# DMXController.net
KiCad netlist of a schematic drawn in Altium Designer
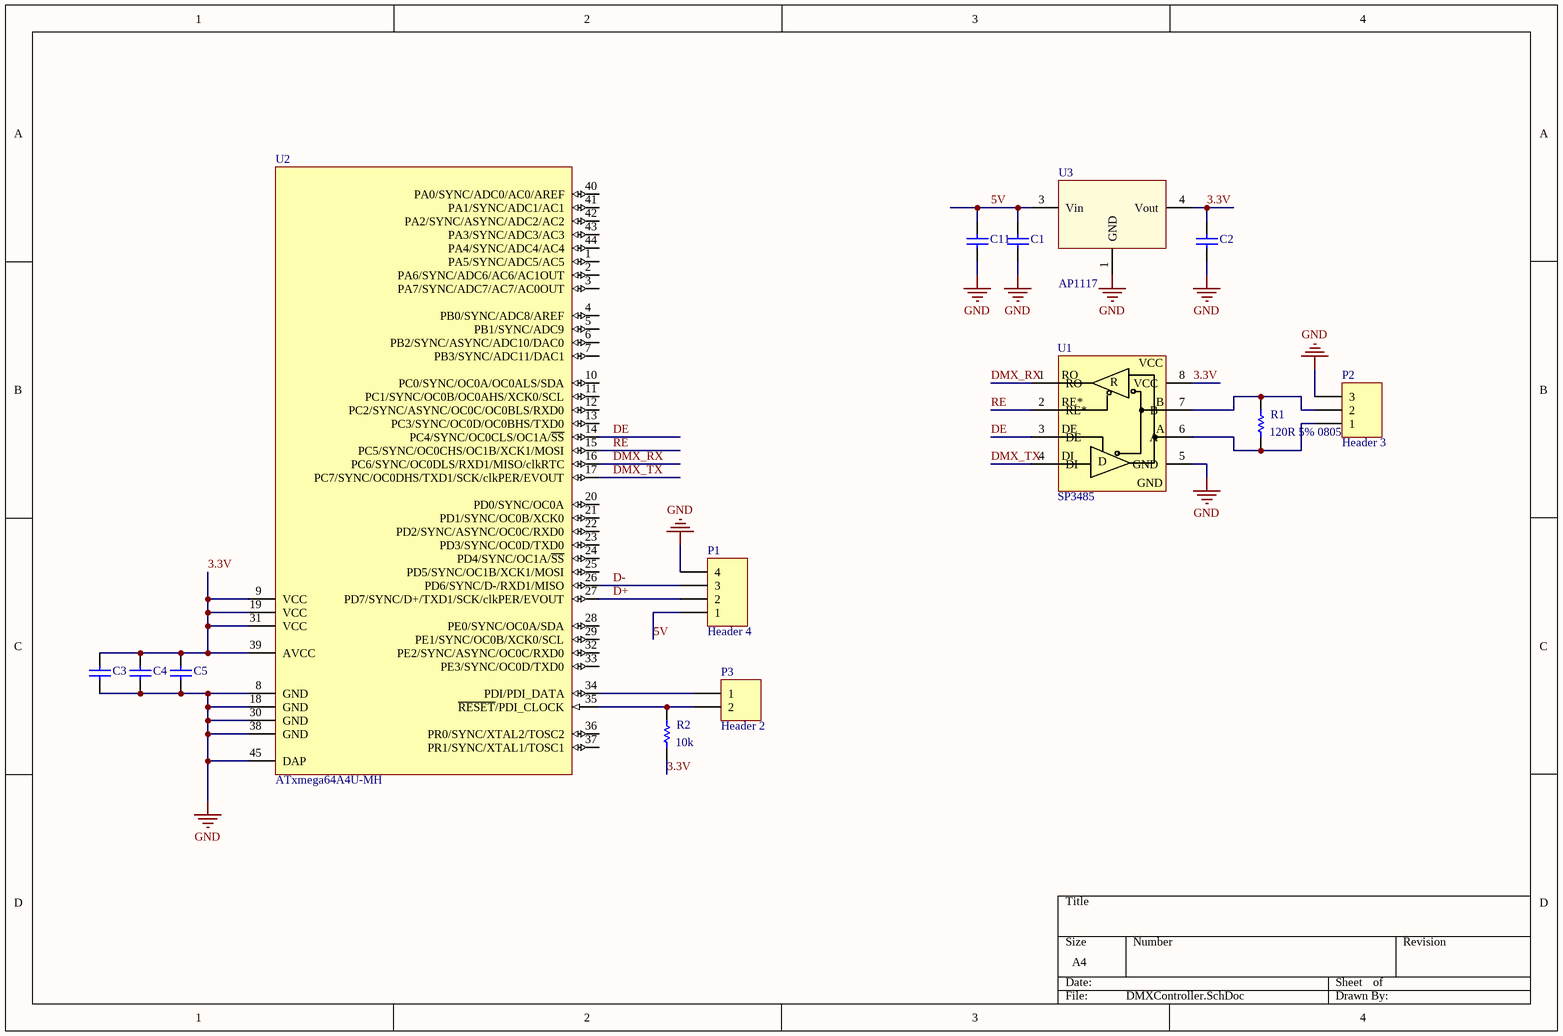
[diagram p0: DMXController.SchDoc]

(export (version "E")
  (design (tool "Eeschema 10.0.6"))
  (components
    (comp (ref "C1")
      (value "10u")
      (footprint "CAPC0805(2012)100_M")
      (description "CAP 1uF 10V ±10% 0805 (2012 Metric) Thickness 1mm SMD")
      (fields (field (name "TOLERANCE") "±10%"))
      (libsource (lib "Altium Content Vault") (part "CMP-1036-04739-1"))
    )
    (comp (ref "C2")
      (value "22u")
      (footprint "CAPC0805(2012)100_M")
      (description "CAP 1uF 10V ±10% 0805 (2012 Metric) Thickness 1mm SMD")
      (fields (field (name "TOLERANCE") "±10%"))
      (libsource (lib "Altium Content Vault") (part "CMP-1036-04739-1"))
    )
    (comp (ref "C3")
      (value "100n")
      (footprint "CAPC0805(2012)100_M")
      (description "CAP 1uF 10V ±10% 0805 (2012 Metric) Thickness 1mm SMD")
      (fields (field (name "TOLERANCE") "±10%"))
      (libsource (lib "Altium Content Vault") (part "CMP-1036-04739-1"))
    )
    (comp (ref "C4")
      (value "100n")
      (footprint "CAPC0805(2012)100_M")
      (description "CAP 1uF 10V ±10% 0805 (2012 Metric) Thickness 1mm SMD")
      (fields (field (name "TOLERANCE") "±10%"))
      (libsource (lib "Altium Content Vault") (part "CMP-1036-04739-1"))
    )
    (comp (ref "C5")
      (value "100n")
      (footprint "CAPC0805(2012)100_M")
      (description "CAP 1uF 10V ±10% 0805 (2012 Metric) Thickness 1mm SMD")
      (fields (field (name "TOLERANCE") "±10%"))
      (libsource (lib "Altium Content Vault") (part "CMP-1036-04739-1"))
    )
    (comp (ref "C11")
      (value "10u")
      (footprint "CAPC0805(2012)100_M")
      (description "CAP 1uF 10V ±10% 0805 (2012 Metric) Thickness 1mm SMD")
      (fields (field (name "TOLERANCE") "±10%"))
      (libsource (lib "Altium Content Vault") (part "CMP-1036-04739-1"))
    )
    (comp (ref "P1")
      (value "Header 4")
      (footprint "HDR1X4")
      (description "Header, 4-Pin")
      (fields (field (name "PUBLISHER") "Altium Limited"))
      (libsource (lib "Miscellaneous Connectors") (part "Header 4"))
    )
    (comp (ref "P2")
      (value "Header 3")
      (footprint "HDR1X3")
      (description "Header, 3-Pin")
      (fields (field (name "PUBLISHER") "Altium Limited"))
      (libsource (lib "Miscellaneous Connectors") (part "Header 3"))
    )
    (comp (ref "P3")
      (value "Header 2")
      (footprint "HDR1X2")
      (description "Header, 2-Pin")
      (fields (field (name "PUBLISHER") "Altium Limited"))
      (libsource (lib "Miscellaneous Connectors") (part "Header 2"))
    )
    (comp (ref "R1")
      (value "120R 5% 0805(2012)")
      (footprint "RESC0805(2012)_N")
      (description "120R 0.125W 5% 0805 (2012 Metric)  SMD")
      (fields (field (name "TOLERANCE") "5 %") (field (name "POWER") "0.125 W"))
      (libsource (lib "Altium Content Vault") (part "RES"))
    )
    (comp (ref "R2")
      (value "10k")
      (footprint "RESC0805(2012)_N")
      (description "120R 0.125W 5% 0805 (2012 Metric)  SMD")
      (fields (field (name "TOLERANCE") "5 %") (field (name "POWER") "0.125 W"))
      (libsource (lib "Altium Content Vault") (part "CMP-1013-00052-1"))
    )
    (comp (ref "U1") (value "SP3485") (footprint "SOIC8") (libsource (lib "Schlib1") (part "SP3485")))
    (comp (ref "U2")
      (value "ATxmega64A4U-MH")
      (footprint "44M1_L")
      (libsource (lib "Altium Content Vault") (part "MC-8B-ATXM16A4U-SQ45"))
    )
    (comp (ref "U3") (value "AP1117") (footprint "SOT-223") (libsource (lib "Schlib1") (part "AP1117")))
  )
  (nets
    (net (code "1") (name "/3.3V") (class "Default")
      (node (ref "C2") (pin "2") (pinfunction "2_2") (pintype "passive"))
      (node (ref "C3") (pin "2") (pinfunction "2_2") (pintype "passive"))
      (node (ref "C4") (pin "2") (pinfunction "2_2") (pintype "passive"))
      (node (ref "C5") (pin "2") (pinfunction "2_2") (pintype "passive"))
      (node (ref "R2") (pin "1") (pinfunction "1_1") (pintype "passive"))
      (node (ref "U1") (pin "8") (pinfunction "VCC_8") (pintype "passive"))
      (node (ref "U2") (pin "19") (pinfunction "VCC_19") (pintype "power_in"))
      (node (ref "U2") (pin "31") (pinfunction "VCC_31") (pintype "power_in"))
      (node (ref "U2") (pin "39") (pinfunction "AVCC_39") (pintype "power_in"))
      (node (ref "U2") (pin "9") (pinfunction "VCC_9") (pintype "power_in"))
      (node (ref "U3") (pin "4") (pinfunction "Vout_4") (pintype "passive"))
    )
    (net (code "2") (name "/5V") (class "Default")
      (node (ref "C1") (pin "2") (pinfunction "2_2") (pintype "passive"))
      (node (ref "C11") (pin "2") (pinfunction "2_2") (pintype "passive"))
      (node (ref "P1") (pin "1") (pinfunction "1_1") (pintype "passive"))
      (node (ref "U3") (pin "3") (pinfunction "Vin_3") (pintype "passive"))
    )
    (net (code "3") (name "/D+") (class "Default")
      (node (ref "P1") (pin "2") (pinfunction "2_2") (pintype "passive"))
      (node (ref "U2") (pin "27") (pinfunction "PD7/SYNC/D+/TXD1/SCK/clkPER/EVOUT_27") (pintype "bidirectional"))
    )
    (net (code "4") (name "/D-") (class "Default")
      (node (ref "P1") (pin "3") (pinfunction "3_3") (pintype "passive"))
      (node (ref "U2") (pin "26") (pinfunction "PD6/SYNC/D-/RXD1/MISO_26") (pintype "bidirectional"))
    )
    (net (code "5") (name "/DE") (class "Default")
      (node (ref "U1") (pin "3") (pinfunction "DE_3") (pintype "passive"))
      (node (ref "U2") (pin "14") (pinfunction "PC4/SYNC/OC0CLS/OC1A/~{SS}_14") (pintype "bidirectional"))
    )
    (net (code "6") (name "/DMX_RX") (class "Default")
      (node (ref "U1") (pin "1") (pinfunction "RO_1") (pintype "passive"))
      (node (ref "U2") (pin "16") (pinfunction "PC6/SYNC/OC0DLS/RXD1/MISO/clkRTC_16") (pintype "bidirectional"))
    )
    (net (code "7") (name "/DMX_TX") (class "Default")
      (node (ref "U1") (pin "4") (pinfunction "DI_4") (pintype "passive"))
      (node (ref "U2") (pin "17") (pinfunction "PC7/SYNC/OC0DHS/TXD1/SCK/clkPER/EVOUT_17") (pintype "bidirectional"))
    )
    (net (code "8") (name "/RE") (class "Default")
      (node (ref "U1") (pin "2") (pinfunction "RE*_2") (pintype "passive"))
      (node (ref "U2") (pin "15") (pinfunction "PC5/SYNC/OC0CHS/OC1B/XCK1/MOSI_15") (pintype "bidirectional"))
    )
    (net (code "9") (name "GND") (class "Default")
      (node (ref "C1") (pin "1") (pinfunction "1_1") (pintype "passive"))
      (node (ref "C11") (pin "1") (pinfunction "1_1") (pintype "passive"))
      (node (ref "C2") (pin "1") (pinfunction "1_1") (pintype "passive"))
      (node (ref "C3") (pin "1") (pinfunction "1_1") (pintype "passive"))
      (node (ref "C4") (pin "1") (pinfunction "1_1") (pintype "passive"))
      (node (ref "C5") (pin "1") (pinfunction "1_1") (pintype "passive"))
      (node (ref "P1") (pin "4") (pinfunction "4_4") (pintype "passive"))
      (node (ref "P2") (pin "3") (pinfunction "3_3") (pintype "passive"))
      (node (ref "U1") (pin "5") (pinfunction "GND_5") (pintype "passive"))
      (node (ref "U2") (pin "18") (pinfunction "GND_18") (pintype "power_in"))
      (node (ref "U2") (pin "30") (pinfunction "GND_30") (pintype "power_in"))
      (node (ref "U2") (pin "38") (pinfunction "GND_38") (pintype "power_in"))
      (node (ref "U2") (pin "45") (pinfunction "DAP_45") (pintype "power_in"))
      (node (ref "U2") (pin "8") (pinfunction "GND_8") (pintype "power_in"))
      (node (ref "U3") (pin "1") (pinfunction "GND_1") (pintype "passive"))
    )
    (net (code "10") (name "Net-(U1-A)") (class "Default")
      (node (ref "P2") (pin "1") (pinfunction "1_1") (pintype "passive"))
      (node (ref "R1") (pin "1") (pinfunction "1_1") (pintype "passive"))
      (node (ref "U1") (pin "6") (pinfunction "A_6") (pintype "passive"))
    )
    (net (code "11") (name "Net-(U1-B)") (class "Default")
      (node (ref "P2") (pin "2") (pinfunction "2_2") (pintype "passive"))
      (node (ref "R1") (pin "2") (pinfunction "2_2") (pintype "passive"))
      (node (ref "U1") (pin "7") (pinfunction "B_7") (pintype "passive"))
    )
    (net (code "12") (name "Net-(U2-PDI{slash}PDI_DATA)") (class "Default")
      (node (ref "P3") (pin "1") (pinfunction "1_1") (pintype "passive"))
      (node (ref "U2") (pin "34") (pinfunction "PDI/PDI_DATA_34") (pintype "bidirectional"))
    )
    (net (code "13") (name "Net-(U2-~{RESET}{slash}PDI_CLOCK)") (class "Default")
      (node (ref "P3") (pin "2") (pinfunction "2_2") (pintype "passive"))
      (node (ref "R2") (pin "2") (pinfunction "2_2") (pintype "passive"))
      (node (ref "U2") (pin "35") (pinfunction "~{RESET}/PDI_CLOCK_35") (pintype "input"))
    )
    (net (code "14") (name "unconnected-(U2-PA0{slash}SYNC{slash}ADC0{slash}AC0{slash}AREF-Pad40)") (class "Default")
      (node (ref "U2") (pin "40") (pinfunction "PA0/SYNC/ADC0/AC0/AREF_40") (pintype "bidirectional"))
    )
    (net (code "15") (name "unconnected-(U2-PA1{slash}SYNC{slash}ADC1{slash}AC1-Pad41)") (class "Default")
      (node (ref "U2") (pin "41") (pinfunction "PA1/SYNC/ADC1/AC1_41") (pintype "bidirectional"))
    )
    (net (code "16") (name "unconnected-(U2-PA2{slash}SYNC{slash}ASYNC{slash}ADC2{slash}AC2-Pad42)") (class "Default")
      (node (ref "U2") (pin "42") (pinfunction "PA2/SYNC/ASYNC/ADC2/AC2_42") (pintype "bidirectional"))
    )
    (net (code "17") (name "unconnected-(U2-PA3{slash}SYNC{slash}ADC3{slash}AC3-Pad43)") (class "Default")
      (node (ref "U2") (pin "43") (pinfunction "PA3/SYNC/ADC3/AC3_43") (pintype "bidirectional"))
    )
    (net (code "18") (name "unconnected-(U2-PA4{slash}SYNC{slash}ADC4{slash}AC4-Pad44)") (class "Default")
      (node (ref "U2") (pin "44") (pinfunction "PA4/SYNC/ADC4/AC4_44") (pintype "bidirectional"))
    )
    (net (code "19") (name "unconnected-(U2-PA5{slash}SYNC{slash}ADC5{slash}AC5-Pad1)") (class "Default")
      (node (ref "U2") (pin "1") (pinfunction "PA5/SYNC/ADC5/AC5_1") (pintype "bidirectional"))
    )
    (net (code "20") (name "unconnected-(U2-PA6{slash}SYNC{slash}ADC6{slash}AC6{slash}AC1OUT-Pad2)") (class "Default")
      (node (ref "U2") (pin "2") (pinfunction "PA6/SYNC/ADC6/AC6/AC1OUT_2") (pintype "bidirectional"))
    )
    (net (code "21") (name "unconnected-(U2-PA7{slash}SYNC{slash}ADC7{slash}AC7{slash}AC0OUT-Pad3)") (class "Default")
      (node (ref "U2") (pin "3") (pinfunction "PA7/SYNC/ADC7/AC7/AC0OUT_3") (pintype "bidirectional"))
    )
    (net (code "22") (name "unconnected-(U2-PB0{slash}SYNC{slash}ADC8{slash}AREF-Pad4)") (class "Default")
      (node (ref "U2") (pin "4") (pinfunction "PB0/SYNC/ADC8/AREF_4") (pintype "bidirectional"))
    )
    (net (code "23") (name "unconnected-(U2-PB1{slash}SYNC{slash}ADC9-Pad5)") (class "Default")
      (node (ref "U2") (pin "5") (pinfunction "PB1/SYNC/ADC9_5") (pintype "bidirectional"))
    )
    (net (code "24") (name "unconnected-(U2-PB2{slash}SYNC{slash}ASYNC{slash}ADC10{slash}DAC0-Pad6)") (class "Default")
      (node (ref "U2") (pin "6") (pinfunction "PB2/SYNC/ASYNC/ADC10/DAC0_6") (pintype "bidirectional"))
    )
    (net (code "25") (name "unconnected-(U2-PB3{slash}SYNC{slash}ADC11{slash}DAC1-Pad7)") (class "Default")
      (node (ref "U2") (pin "7") (pinfunction "PB3/SYNC/ADC11/DAC1_7") (pintype "bidirectional"))
    )
    (net (code "26") (name "unconnected-(U2-PC0{slash}SYNC{slash}OC0A{slash}OC0ALS{slash}SDA-Pad10)") (class "Default")
      (node (ref "U2") (pin "10") (pinfunction "PC0/SYNC/OC0A/OC0ALS/SDA_10") (pintype "bidirectional"))
    )
    (net (code "27") (name "unconnected-(U2-PC1{slash}SYNC{slash}OC0B{slash}OC0AHS{slash}XCK0{slash}SCL-Pad11)") (class "Default")
      (node (ref "U2") (pin "11") (pinfunction "PC1/SYNC/OC0B/OC0AHS/XCK0/SCL_11") (pintype "bidirectional"))
    )
    (net (code "28") (name "unconnected-(U2-PC2{slash}SYNC{slash}ASYNC{slash}OC0C{slash}OC0BLS{slash}RXD0-Pad12)") (class "Default")
      (node (ref "U2") (pin "12") (pinfunction "PC2/SYNC/ASYNC/OC0C/OC0BLS/RXD0_12") (pintype "bidirectional"))
    )
    (net (code "29") (name "unconnected-(U2-PC3{slash}SYNC{slash}OC0D{slash}OC0BHS{slash}TXD0-Pad13)") (class "Default")
      (node (ref "U2") (pin "13") (pinfunction "PC3/SYNC/OC0D/OC0BHS/TXD0_13") (pintype "bidirectional"))
    )
    (net (code "30") (name "unconnected-(U2-PD0{slash}SYNC{slash}OC0A-Pad20)") (class "Default")
      (node (ref "U2") (pin "20") (pinfunction "PD0/SYNC/OC0A_20") (pintype "bidirectional"))
    )
    (net (code "31") (name "unconnected-(U2-PD1{slash}SYNC{slash}OC0B{slash}XCK0-Pad21)") (class "Default")
      (node (ref "U2") (pin "21") (pinfunction "PD1/SYNC/OC0B/XCK0_21") (pintype "bidirectional"))
    )
    (net (code "32") (name "unconnected-(U2-PD2{slash}SYNC{slash}ASYNC{slash}OC0C{slash}RXD0-Pad22)") (class "Default")
      (node (ref "U2") (pin "22") (pinfunction "PD2/SYNC/ASYNC/OC0C/RXD0_22") (pintype "bidirectional"))
    )
    (net (code "33") (name "unconnected-(U2-PD3{slash}SYNC{slash}OC0D{slash}TXD0-Pad23)") (class "Default")
      (node (ref "U2") (pin "23") (pinfunction "PD3/SYNC/OC0D/TXD0_23") (pintype "bidirectional"))
    )
    (net (code "34") (name "unconnected-(U2-PD4{slash}SYNC{slash}OC1A{slash}~{SS}-Pad24)") (class "Default")
      (node (ref "U2") (pin "24") (pinfunction "PD4/SYNC/OC1A/~{SS}_24") (pintype "bidirectional"))
    )
    (net (code "35") (name "unconnected-(U2-PD5{slash}SYNC{slash}OC1B{slash}XCK1{slash}MOSI-Pad25)") (class "Default")
      (node (ref "U2") (pin "25") (pinfunction "PD5/SYNC/OC1B/XCK1/MOSI_25") (pintype "bidirectional"))
    )
    (net (code "36") (name "unconnected-(U2-PE0{slash}SYNC{slash}OC0A{slash}SDA-Pad28)") (class "Default")
      (node (ref "U2") (pin "28") (pinfunction "PE0/SYNC/OC0A/SDA_28") (pintype "bidirectional"))
    )
    (net (code "37") (name "unconnected-(U2-PE1{slash}SYNC{slash}OC0B{slash}XCK0{slash}SCL-Pad29)") (class "Default")
      (node (ref "U2") (pin "29") (pinfunction "PE1/SYNC/OC0B/XCK0/SCL_29") (pintype "bidirectional"))
    )
    (net (code "38") (name "unconnected-(U2-PE2{slash}SYNC{slash}ASYNC{slash}OC0C{slash}RXD0-Pad32)") (class "Default")
      (node (ref "U2") (pin "32") (pinfunction "PE2/SYNC/ASYNC/OC0C/RXD0_32") (pintype "bidirectional"))
    )
    (net (code "39") (name "unconnected-(U2-PE3{slash}SYNC{slash}OC0D{slash}TXD0-Pad33)") (class "Default")
      (node (ref "U2") (pin "33") (pinfunction "PE3/SYNC/OC0D/TXD0_33") (pintype "bidirectional"))
    )
    (net (code "40") (name "unconnected-(U2-PR0{slash}SYNC{slash}XTAL2{slash}TOSC2-Pad36)") (class "Default")
      (node (ref "U2") (pin "36") (pinfunction "PR0/SYNC/XTAL2/TOSC2_36") (pintype "bidirectional"))
    )
    (net (code "41") (name "unconnected-(U2-PR1{slash}SYNC{slash}XTAL1{slash}TOSC1-Pad37)") (class "Default")
      (node (ref "U2") (pin "37") (pinfunction "PR1/SYNC/XTAL1/TOSC1_37") (pintype "bidirectional"))
    )
  )
)
